# sch_ma_TC1.net
KiCad netlist of a schematic drawn in Altium Designer
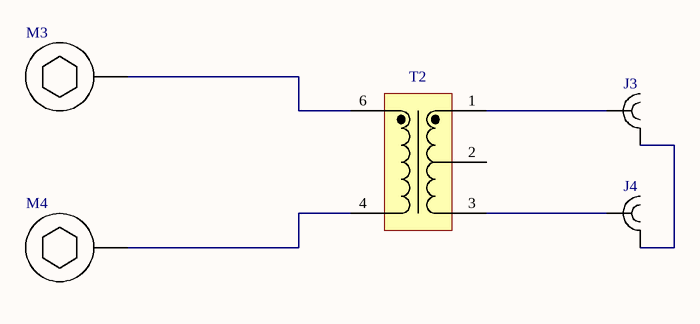
[diagram p0: schéma_TC1.SchDoc]

(export (version "E")
  (design (tool "Eeschema 10.0.6"))
  (components
    (comp (ref "J3")
      (value "CONSMA001-G")
      (footprint "SMA TH Vertical Linx CONSMA001-G")
      (description "SMA TH VERTICAL LINX CONSMA001-G")
      (libsource (lib "Connector") (part "SMA TH VERTICAL LINX CONSMA001-G"))
    )
    (comp (ref "J4")
      (value "CONSMA001-G")
      (footprint "SMA TH Vertical Linx CONSMA001-G")
      (description "SMA TH VERTICAL LINX CONSMA001-G")
      (libsource (lib "Connector") (part "SMA TH VERTICAL LINX CONSMA001-G"))
    )
    (comp (ref "M3")
      (value "~")
      (footprint "Screw Hex Socket M2.5X4 Connected")
      (description "Screw Hex Socket Connected BN610")
      (libsource (lib "Mechanic") (part "Screw Hex Socket Connected"))
    )
    (comp (ref "M4")
      (value "~")
      (footprint "Screw Hex Socket M2.5X4 Connected")
      (description "Screw Hex Socket Connected BN610")
      (libsource (lib "Mechanic") (part "Screw Hex Socket Connected"))
    )
    (comp (ref "T2")
      (value "{Value}")
      (footprint "TC1-1TG2+")
      (description "Mini-Circuits RF Transformer")
      (libsource (lib "Transformer") (part "TC1-1TG2+"))
    )
  )
  (nets
    (net (code "1") (name "Net-(J3-Pad1)") (class "Default")
      (node (ref "J3") (pin "1") (pinfunction "1_1") (pintype "passive"))
      (node (ref "T2") (pin "1") (pinfunction "1_1") (pintype "passive"))
    )
    (net (code "2") (name "Net-(J3-Pad2)") (class "Default")
      (node (ref "J3") (pin "2") (pinfunction "2_2") (pintype "passive"))
      (node (ref "J4") (pin "2") (pinfunction "2_2") (pintype "passive"))
    )
    (net (code "3") (name "Net-(J4-Pad1)") (class "Default")
      (node (ref "J4") (pin "1") (pinfunction "1_1") (pintype "passive"))
      (node (ref "T2") (pin "3") (pinfunction "3_3") (pintype "passive"))
    )
    (net (code "4") (name "Net-(M3-Pad1)") (class "Default")
      (node (ref "M3") (pin "1") (pinfunction "1_1") (pintype "passive"))
      (node (ref "T2") (pin "6") (pinfunction "6_6") (pintype "passive"))
    )
    (net (code "5") (name "Net-(M4-Pad1)") (class "Default")
      (node (ref "M4") (pin "1") (pinfunction "1_1") (pintype "passive"))
      (node (ref "T2") (pin "4") (pinfunction "4_4") (pintype "passive"))
    )
    (net (code "6") (name "unconnected-(T2-Pad2)") (class "Default")
      (node (ref "T2") (pin "2") (pinfunction "2_2") (pintype "passive"))
    )
  )
)
